# GPS.net
KiCad netlist of a schematic drawn in Altium Designer
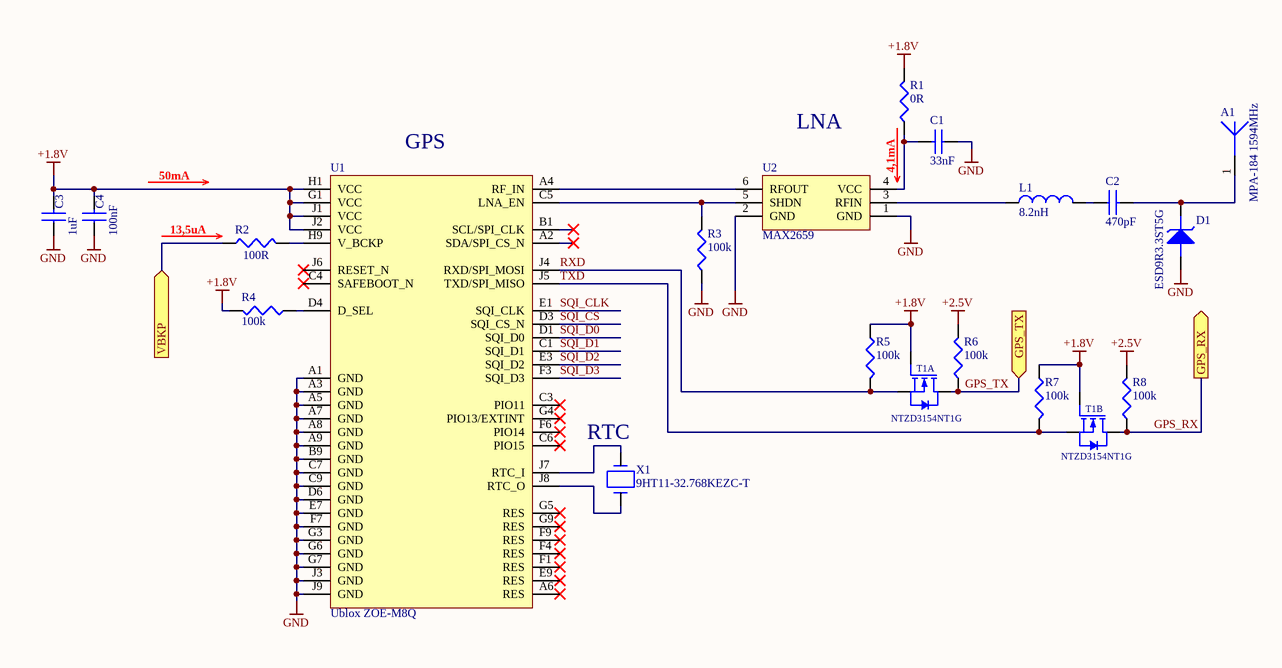
[diagram p0: GPS.SchDoc]

(export (version "E")
  (design (tool "Eeschema 10.0.6"))
  (components
    (comp (ref "A1")
      (value "MPA-184 1594MHz")
      (footprint "MPA-184")
      (description "Antennas Passive GPS/GLONASS Patch Antenna")
      (fields (field (name "MANUFACTURER") "Antenova") (field (name "MANUFACTURER PART NUMBER") "SR42I010-R"))
      (libsource (lib "Passive") (part "ANT - MAXTENA MPA-184 1594MHz"))
    )
    (comp (ref "C1")
      (value "33nF")
      (footprint "CAP0402")
      (fields
        (field (name "MANUFACTURER") "Multicomp")
        (field (name "MANUFACTURER PART NUMBER") "MC0402N330J160CT")
        (field (name "TOLERANCE") "5%")
      )
      (libsource (lib "Passive") (part "C - 33pF/0402"))
    )
    (comp (ref "C2")
      (value "470pF")
      (footprint "CAP0402")
      (fields
        (field (name "MANUFACTURER") "Murata")
        (field (name "MANUFACTURER PART NUMBER") "GRT155R71H471KE01D")
        (field (name "IRNAS PART NO.") "/")
      )
      (libsource (lib "Passive") (part "C - 470pF/0402"))
    )
    (comp (ref "C3")
      (value "1uF")
      (footprint "CAP0402")
      (description "CAP CER 1UF 10V 20% X5R 0402")
      (fields
        (field (name "MANUFACTURER") "Murata")
        (field (name "MANUFACTURER PART NUMBER") "GRM155R61A105ME15D")
      )
      (libsource (lib "Passive") (part "C - 1uF/0402"))
    )
    (comp (ref "C4")
      (value "100nF")
      (footprint "CAP0402")
      (fields
        (field (name "MANUFACTURER") "Multicomp")
        (field (name "MANUFACTURER PART NUMBER") "MC0402X104J160CT")
        (field (name "TOLERANCE") "5%")
      )
      (libsource (lib "Passive") (part "C - 100nF/0402"))
    )
    (comp (ref "D1")
      (value "ESD9R3.3ST5G")
      (footprint "SOD-923")
      (description "TVS Diode, ESD9R Series, Unidirectional, 3.3 V, 7.8 V")
      (fields
        (field (name "MANUFACTURER") "DIODES INC.")
        (field (name "MANUFACTURER PART NUMBER") "1N4148W-7-F.")
      )
      (libsource (lib "Active") (part "D_TVS - ESD9R3.3ST5G"))
    )
    (comp (ref "L1")
      (value "8.2nH")
      (footprint "IND0402")
      (description "FIXED IND 33NH 200MA 580 MOHM")
      (fields
        (field (name "MANUFACTURER") "Murata")
        (field (name "MANUFACTURER PART NUMBER") "LQG15HS33NJ02D")
      )
      (libsource (lib "Passive") (part "L - 33nH/0402"))
    )
    (comp (ref "R1")
      (value "0R")
      (footprint "RES0402")
      (description "RESISTOR, 0402, 0R, ANTI SULFURATION")
      (fields
        (field (name "MANUFACTURER") "Multicomp")
        (field (name "MANUFACTURER PART NUMBER") "MCMR04X000PTL")
      )
      (libsource (lib "Passive") (part "R - 0R/0402"))
    )
    (comp (ref "R2")
      (value "100R")
      (footprint "RES0402")
      (fields
        (field (name "MANUFACTURER") "Multicomp")
        (field (name "MANUFACTURER PART NUMBER") "MCMR04X1000FTL")
        (field (name "TOLERANCE") "1%")
      )
      (libsource (lib "Passive") (part "R - 100R/0402"))
    )
    (comp (ref "R3")
      (value "100k")
      (footprint "RES0402")
      (description "MULTICOMP   MCWR04X1003FTL   RES, THICK FILM, 100KOHM, 1%, 0.0625W")
      (fields
        (field (name "MANUFACTURER") "Multicomp")
        (field (name "MANUFACTURER PART NUMBER") "MCWR04X1003FTL")
      )
      (libsource (lib "Passive") (part "R - 100k/0402"))
    )
    (comp (ref "R4")
      (value "100k")
      (footprint "RES0402")
      (description "MULTICOMP   MCWR04X1003FTL   RES, THICK FILM, 100KOHM, 1%, 0.0625W")
      (fields
        (field (name "MANUFACTURER") "Multicomp")
        (field (name "MANUFACTURER PART NUMBER") "MCWR04X1003FTL")
      )
      (libsource (lib "Passive") (part "R - 100k/0402"))
    )
    (comp (ref "R5")
      (value "100k")
      (footprint "RES0402")
      (description "MULTICOMP   MCWR04X1003FTL   RES, THICK FILM, 100KOHM, 1%, 0.0625W")
      (fields
        (field (name "MANUFACTURER") "Multicomp")
        (field (name "MANUFACTURER PART NUMBER") "MCWR04X1003FTL")
      )
      (libsource (lib "Passive") (part "R - 100k/0402"))
    )
    (comp (ref "R6")
      (value "100k")
      (footprint "RES0402")
      (description "MULTICOMP   MCWR04X1003FTL   RES, THICK FILM, 100KOHM, 1%, 0.0625W")
      (fields
        (field (name "MANUFACTURER") "Multicomp")
        (field (name "MANUFACTURER PART NUMBER") "MCWR04X1003FTL")
      )
      (libsource (lib "Passive") (part "R - 100k/0402"))
    )
    (comp (ref "R7")
      (value "100k")
      (footprint "RES0402")
      (description "MULTICOMP   MCWR04X1003FTL   RES, THICK FILM, 100KOHM, 1%, 0.0625W")
      (fields
        (field (name "MANUFACTURER") "Multicomp")
        (field (name "MANUFACTURER PART NUMBER") "MCWR04X1003FTL")
      )
      (libsource (lib "Passive") (part "R - 100k/0402"))
    )
    (comp (ref "R8")
      (value "100k")
      (footprint "RES0402")
      (description "MULTICOMP   MCWR04X1003FTL   RES, THICK FILM, 100KOHM, 1%, 0.0625W")
      (fields
        (field (name "MANUFACTURER") "Multicomp")
        (field (name "MANUFACTURER PART NUMBER") "MCWR04X1003FTL")
      )
      (libsource (lib "Passive") (part "R - 100k/0402"))
    )
    (comp (ref "T1")
      (value "NTZD3154NT1G")
      (footprint "SOT-563")
      (description "Dual MOSFET, Dual N Channel, 540 mA, 20 V, 0.4 ohm, 4.5 V, 1 V")
      (fields (field (name "AUTHOR") "Ciril Golob"))
      (libsource (lib "Active") (part "T_M - NTZD3154NT1G"))
    )
    (comp (ref "U1")
      (value "Ublox ZOE-M8Q")
      (footprint "S-LGA51")
      (description "ZOE-M8 RF Receiver BeiDou, Galileo, GLONASS, GNSS, GPS -160dBm")
      (fields (field (name "MANUFACTURER") "u-blox") (field (name "MANUFACTURER PART NUMBER") "MAX-M8Q-0"))
      (libsource (lib "Active") (part "RF - UBLOX-ZOE-M8B"))
    )
    (comp (ref "U2")
      (value "MAX2659")
      (footprint "uDFN-6")
      (description "RF Amplifier, GPS / GNSS, 20.5 dB Gain / 0.8 dB Noise, 1575.42 MHz, 1.6 V to 3.3 V Supply")
      (fields (field (name "MANUFACTURER") "u-blox") (field (name "MANUFACTURER PART NUMBER") "MAX-M8Q-0"))
      (libsource (lib "Active") (part "RF - MAX2659"))
    )
    (comp (ref "X1")
      (value "9HT11-32.768KEZC-T")
      (footprint "9HT11")
      (description "Crystal, 32.768 kHz, SMD, 2mm x 1.2mm, 9 pF, 10 ppm, 9HT11 Series")
      (fields (field (name "MANUFACTURER") "IQD") (field (name "MANUFACTURER PART NUMBER") "LFXTAL009678"))
      (libsource (lib "Passive") (part "X - 9HT11-32.768KEZC-T"))
    )
  )
  (nets
    (net (code "1") (name "+1.8V") (class "Default")
      (node (ref "C3") (pin "2") (pinfunction "2_2") (pintype "passive"))
      (node (ref "C4") (pin "2") (pinfunction "2_2") (pintype "passive"))
      (node (ref "R1") (pin "2") (pinfunction "2_2") (pintype "passive"))
      (node (ref "R4") (pin "2") (pinfunction "2_2") (pintype "passive"))
      (node (ref "R5") (pin "1") (pinfunction "1_1") (pintype "passive"))
      (node (ref "R7") (pin "1") (pinfunction "1_1") (pintype "passive"))
      (node (ref "T1") (pin "2") (pinfunction "G1_2") (pintype "passive"))
      (node (ref "T1") (pin "5") (pinfunction "G2_5") (pintype "passive"))
      (node (ref "U1") (pin "G1") (pinfunction "VCC_G1") (pintype "passive"))
      (node (ref "U1") (pin "H1") (pinfunction "VCC_H1") (pintype "passive"))
      (node (ref "U1") (pin "J1") (pinfunction "VCC_J1") (pintype "passive"))
      (node (ref "U1") (pin "J2") (pinfunction "VCC_J2") (pintype "passive"))
    )
    (net (code "2") (name "+2.5V") (class "Default")
      (node (ref "R6") (pin "2") (pinfunction "2_2") (pintype "passive"))
      (node (ref "R8") (pin "2") (pinfunction "2_2") (pintype "passive"))
    )
    (net (code "3") (name "/GPS_RX") (class "Default")
      (node (ref "R8") (pin "1") (pinfunction "1_1") (pintype "passive"))
      (node (ref "T1") (pin "3") (pinfunction "D2_3") (pintype "passive"))
    )
    (net (code "4") (name "/GPS_TX") (class "Default")
      (node (ref "R6") (pin "1") (pinfunction "1_1") (pintype "passive"))
      (node (ref "T1") (pin "6") (pinfunction "D1_6") (pintype "passive"))
    )
    (net (code "5") (name "/RXD") (class "Default")
      (node (ref "R5") (pin "2") (pinfunction "2_2") (pintype "passive"))
      (node (ref "T1") (pin "1") (pinfunction "S1_1") (pintype "passive"))
      (node (ref "U1") (pin "J4") (pinfunction "RXD/SPI_MOSI_J4") (pintype "passive"))
    )
    (net (code "6") (name "/SQI_CLK") (class "Default")
      (node (ref "U1") (pin "E1") (pinfunction "SQI_CLK_E1") (pintype "passive"))
    )
    (net (code "7") (name "/SQI_CS") (class "Default")
      (node (ref "U1") (pin "D3") (pinfunction "SQI_CS_N_D3") (pintype "passive"))
    )
    (net (code "8") (name "/SQI_D0") (class "Default")
      (node (ref "U1") (pin "D1") (pinfunction "SQI_D0_D1") (pintype "passive"))
    )
    (net (code "9") (name "/SQI_D1") (class "Default")
      (node (ref "U1") (pin "C1") (pinfunction "SQI_D1_C1") (pintype "passive"))
    )
    (net (code "10") (name "/SQI_D2") (class "Default")
      (node (ref "U1") (pin "E3") (pinfunction "SQI_D2_E3") (pintype "passive"))
    )
    (net (code "11") (name "/SQI_D3") (class "Default")
      (node (ref "U1") (pin "F3") (pinfunction "SQI_D3_F3") (pintype "passive"))
    )
    (net (code "12") (name "/TXD") (class "Default")
      (node (ref "R7") (pin "2") (pinfunction "2_2") (pintype "passive"))
      (node (ref "T1") (pin "4") (pinfunction "S2_4") (pintype "passive"))
      (node (ref "U1") (pin "J5") (pinfunction "TXD/SPI_MISO_J5") (pintype "passive"))
    )
    (net (code "13") (name "/VBKP") (class "Default")
      (node (ref "R2") (pin "1") (pinfunction "1_1") (pintype "passive"))
    )
    (net (code "14") (name "GND") (class "Default")
      (node (ref "C1") (pin "1") (pinfunction "1_1") (pintype "passive"))
      (node (ref "C3") (pin "1") (pinfunction "1_1") (pintype "passive"))
      (node (ref "C4") (pin "1") (pinfunction "1_1") (pintype "passive"))
      (node (ref "D1") (pin "A") (pinfunction "ANODE_A") (pintype "passive"))
      (node (ref "R3") (pin "1") (pinfunction "1_1") (pintype "passive"))
      (node (ref "U1") (pin "A1") (pinfunction "GND_A1") (pintype "passive"))
      (node (ref "U1") (pin "A3") (pinfunction "GND_A3") (pintype "passive"))
      (node (ref "U1") (pin "A5") (pinfunction "GND_A5") (pintype "passive"))
      (node (ref "U1") (pin "A7") (pinfunction "GND_A7") (pintype "passive"))
      (node (ref "U1") (pin "A8") (pinfunction "GND_A8") (pintype "passive"))
      (node (ref "U1") (pin "A9") (pinfunction "GND_A9") (pintype "passive"))
      (node (ref "U1") (pin "B9") (pinfunction "GND_B9") (pintype "passive"))
      (node (ref "U1") (pin "C7") (pinfunction "GND_C7") (pintype "passive"))
      (node (ref "U1") (pin "C9") (pinfunction "GND_C9") (pintype "passive"))
      (node (ref "U1") (pin "D6") (pinfunction "GND_D6") (pintype "passive"))
      (node (ref "U1") (pin "E7") (pinfunction "GND_E7") (pintype "passive"))
      (node (ref "U1") (pin "F7") (pinfunction "GND_F7") (pintype "passive"))
      (node (ref "U1") (pin "G3") (pinfunction "GND_G3") (pintype "passive"))
      (node (ref "U1") (pin "G6") (pinfunction "GND_G6") (pintype "passive"))
      (node (ref "U1") (pin "G7") (pinfunction "GND_G7") (pintype "passive"))
      (node (ref "U1") (pin "J3") (pinfunction "GND_J3") (pintype "passive"))
      (node (ref "U1") (pin "J9") (pinfunction "GND_J9") (pintype "passive"))
      (node (ref "U2") (pin "1") (pinfunction "GND_1") (pintype "passive"))
      (node (ref "U2") (pin "2") (pinfunction "GND_2") (pintype "passive"))
    )
    (net (code "15") (name "Net-(A1-ANT)") (class "Default")
      (node (ref "A1") (pin "1") (pinfunction "ANT_1") (pintype "passive"))
      (node (ref "C2") (pin "2") (pinfunction "2_2") (pintype "passive"))
      (node (ref "D1") (pin "K") (pinfunction "cathode_K") (pintype "passive"))
    )
    (net (code "16") (name "Net-(C2-Pad1)") (class "Default")
      (node (ref "C2") (pin "1") (pinfunction "1_1") (pintype "passive"))
      (node (ref "L1") (pin "2") (pinfunction "2_2") (pintype "passive"))
    )
    (net (code "17") (name "Net-(U1-D_SEL)") (class "Default")
      (node (ref "R4") (pin "1") (pinfunction "1_1") (pintype "passive"))
      (node (ref "U1") (pin "D4") (pinfunction "D_SEL_D4") (pintype "passive"))
    )
    (net (code "18") (name "Net-(U1-LNA_EN)") (class "Default")
      (node (ref "R3") (pin "2") (pinfunction "2_2") (pintype "passive"))
      (node (ref "U1") (pin "C5") (pinfunction "LNA_EN_C5") (pintype "passive"))
      (node (ref "U2") (pin "5") (pinfunction "SHDN_5") (pintype "passive"))
    )
    (net (code "19") (name "Net-(U1-RF_IN)") (class "Default")
      (node (ref "U1") (pin "A4") (pinfunction "RF_IN_A4") (pintype "passive"))
      (node (ref "U2") (pin "6") (pinfunction "RFOUT_6") (pintype "passive"))
    )
    (net (code "20") (name "Net-(U1-RTC_I)") (class "Default")
      (node (ref "U1") (pin "J7") (pinfunction "RTC_I_J7") (pintype "passive"))
      (node (ref "X1") (pin "2") (pinfunction "2_2") (pintype "passive"))
    )
    (net (code "21") (name "Net-(U1-RTC_O)") (class "Default")
      (node (ref "U1") (pin "J8") (pinfunction "RTC_O_J8") (pintype "passive"))
      (node (ref "X1") (pin "1") (pinfunction "1_1") (pintype "passive"))
    )
    (net (code "22") (name "Net-(U1-V_BCKP)") (class "Default")
      (node (ref "R2") (pin "2") (pinfunction "2_2") (pintype "passive"))
      (node (ref "U1") (pin "H9") (pinfunction "V_BCKP_H9") (pintype "passive"))
    )
    (net (code "23") (name "Net-(U2-RFIN)") (class "Default")
      (node (ref "L1") (pin "1") (pinfunction "1_1") (pintype "passive"))
      (node (ref "U2") (pin "3") (pinfunction "RFIN_3") (pintype "passive"))
    )
    (net (code "24") (name "Net-(U2-VCC)") (class "Default")
      (node (ref "C1") (pin "2") (pinfunction "2_2") (pintype "passive"))
      (node (ref "R1") (pin "1") (pinfunction "1_1") (pintype "passive"))
      (node (ref "U2") (pin "4") (pinfunction "VCC_4") (pintype "passive"))
    )
    (net (code "25") (name "unconnected-(U1-PIO11-PadC3)") (class "Default")
      (node (ref "U1") (pin "C3") (pinfunction "PIO11_C3") (pintype "passive+no_connect"))
    )
    (net (code "26") (name "unconnected-(U1-PIO13{slash}EXTINT-PadG4)") (class "Default")
      (node (ref "U1") (pin "G4") (pinfunction "PIO13/EXTINT_G4") (pintype "passive+no_connect"))
    )
    (net (code "27") (name "unconnected-(U1-PIO14-PadF6)") (class "Default")
      (node (ref "U1") (pin "F6") (pinfunction "PIO14_F6") (pintype "passive+no_connect"))
    )
    (net (code "28") (name "unconnected-(U1-PIO15-PadC6)") (class "Default")
      (node (ref "U1") (pin "C6") (pinfunction "PIO15_C6") (pintype "passive+no_connect"))
    )
    (net (code "29") (name "unconnected-(U1-RES-PadA6)") (class "Default")
      (node (ref "U1") (pin "A6") (pinfunction "RES_A6") (pintype "passive+no_connect"))
    )
    (net (code "30") (name "unconnected-(U1-RES-PadE9)") (class "Default")
      (node (ref "U1") (pin "E9") (pinfunction "RES_E9") (pintype "passive+no_connect"))
    )
    (net (code "31") (name "unconnected-(U1-RES-PadF1)") (class "Default")
      (node (ref "U1") (pin "F1") (pinfunction "RES_F1") (pintype "passive+no_connect"))
    )
    (net (code "32") (name "unconnected-(U1-RES-PadF4)") (class "Default")
      (node (ref "U1") (pin "F4") (pinfunction "RES_F4") (pintype "passive+no_connect"))
    )
    (net (code "33") (name "unconnected-(U1-RES-PadF9)") (class "Default")
      (node (ref "U1") (pin "F9") (pinfunction "RES_F9") (pintype "passive+no_connect"))
    )
    (net (code "34") (name "unconnected-(U1-RES-PadG5)") (class "Default")
      (node (ref "U1") (pin "G5") (pinfunction "RES_G5") (pintype "passive+no_connect"))
    )
    (net (code "35") (name "unconnected-(U1-RES-PadG9)") (class "Default")
      (node (ref "U1") (pin "G9") (pinfunction "RES_G9") (pintype "passive+no_connect"))
    )
    (net (code "36") (name "unconnected-(U1-RESET_N-PadJ6)") (class "Default")
      (node (ref "U1") (pin "J6") (pinfunction "RESET_N_J6") (pintype "passive+no_connect"))
    )
    (net (code "37") (name "unconnected-(U1-SAFEBOOT_N-PadC4)") (class "Default")
      (node (ref "U1") (pin "C4") (pinfunction "SAFEBOOT_N_C4") (pintype "passive+no_connect"))
    )
    (net (code "38") (name "unconnected-(U1-SCL{slash}SPI_CLK-PadB1)") (class "Default")
      (node (ref "U1") (pin "B1") (pinfunction "SCL/SPI_CLK_B1") (pintype "passive+no_connect"))
    )
    (net (code "39") (name "unconnected-(U1-SDA{slash}SPI_CS_N-PadA2)") (class "Default")
      (node (ref "U1") (pin "A2") (pinfunction "SDA/SPI_CS_N_A2") (pintype "passive+no_connect"))
    )
  )
)
